# LightFlasher.net
KiCad netlist of a schematic drawn in EAGLE
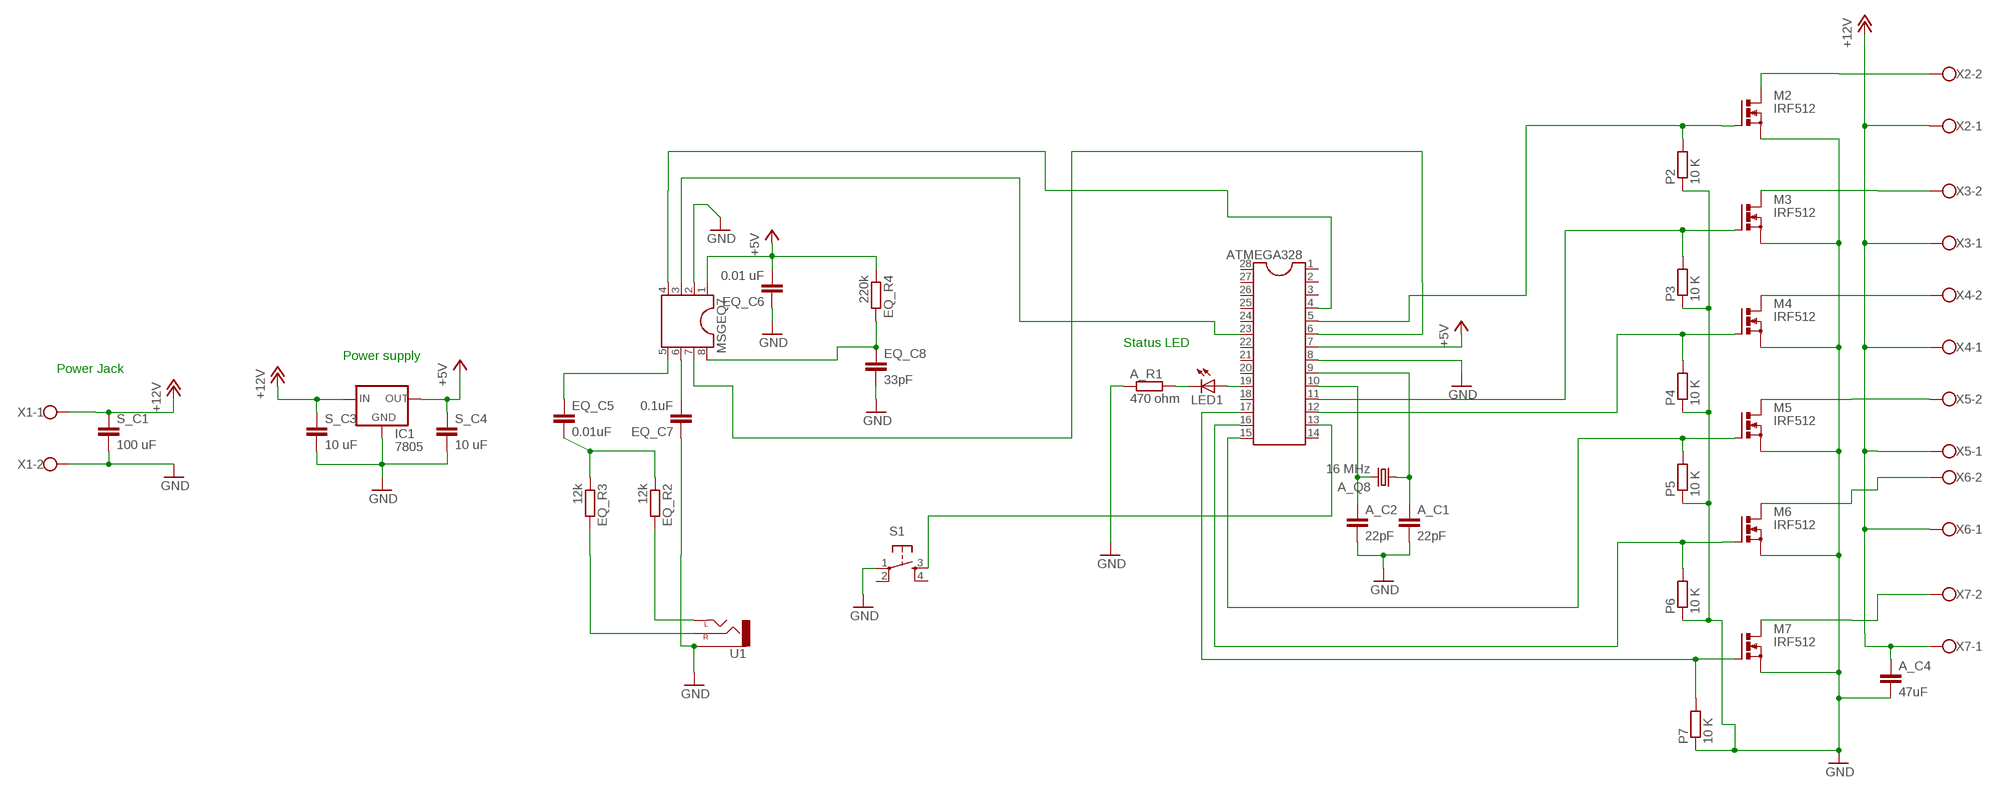
[diagram p0: schematic, sheet 1]

(export (version "E")
  (design (tool "Eeschema 10.0.6"))
  (components
    (comp (ref "ATMEGA328")
      (value "DIL28-3")
      (footprint "eagle-import:DIL28-3")
      (libsource (lib "eagle-import") (part "DIL28-3"))
    )
    (comp (ref "A_C1")
      (value "22pF")
      (footprint "eagle-import:C025-024X044")
      (libsource (lib "eagle-import") (part "C-EU025-024X044"))
    )
    (comp (ref "A_C2")
      (value "22pF")
      (footprint "eagle-import:C050-030X075")
      (libsource (lib "eagle-import") (part "C-EU050-030X075"))
    )
    (comp (ref "A_C4")
      (value "47uF")
      (footprint "eagle-import:C025-025X050")
      (libsource (lib "eagle-import") (part "C-EU025-025X050"))
    )
    (comp (ref "A_Q8")
      (value "16 MHz")
      (footprint "eagle-import:HC49_S")
      (libsource (lib "eagle-import") (part "CRYSTALHC49S"))
    )
    (comp (ref "A_R1")
      (value "470 ohm")
      (footprint "eagle-import:0204_5")
      (libsource (lib "eagle-import") (part "R-EU_0204/5"))
    )
    (comp (ref "EQ_C5")
      (value "0.01uF")
      (footprint "eagle-import:C025-024X044")
      (libsource (lib "eagle-import") (part "C-EU025-024X044"))
    )
    (comp (ref "EQ_C6")
      (value "0.01 uF")
      (footprint "eagle-import:C025-024X044")
      (libsource (lib "eagle-import") (part "C-EU025-024X044"))
    )
    (comp (ref "EQ_C7")
      (value "0.1uF")
      (footprint "eagle-import:C025-024X044")
      (libsource (lib "eagle-import") (part "C-EU025-024X044"))
    )
    (comp (ref "EQ_C8")
      (value "33pF")
      (footprint "eagle-import:C025-024X044")
      (libsource (lib "eagle-import") (part "C-EU025-024X044"))
    )
    (comp (ref "EQ_R2")
      (value "12k")
      (footprint "eagle-import:0204_5")
      (libsource (lib "eagle-import") (part "R-EU_0204/5"))
    )
    (comp (ref "EQ_R3")
      (value "12k")
      (footprint "eagle-import:0204_5")
      (libsource (lib "eagle-import") (part "R-EU_0204/5"))
    )
    (comp (ref "EQ_R4")
      (value "220k")
      (footprint "eagle-import:0204_5")
      (libsource (lib "eagle-import") (part "R-EU_0204/5"))
    )
    (comp (ref "IC1")
      (value "7805")
      (footprint "eagle-import:78XXS")
      (libsource (lib "eagle-import") (part "78XXS"))
    )
    (comp (ref "LED1")
      (value "LED3MM")
      (footprint "eagle-import:LED3MM")
      (libsource (lib "eagle-import") (part "LED3MM"))
    )
    (comp (ref "M2")
      (value "IRF512")
      (footprint "eagle-import:TO220BV")
      (libsource (lib "eagle-import") (part "IRF512"))
    )
    (comp (ref "M3")
      (value "IRF512")
      (footprint "eagle-import:TO220BV")
      (libsource (lib "eagle-import") (part "IRF512"))
    )
    (comp (ref "M4")
      (value "IRF512")
      (footprint "eagle-import:TO220BV")
      (libsource (lib "eagle-import") (part "IRF512"))
    )
    (comp (ref "M5")
      (value "IRF512")
      (footprint "eagle-import:TO220BV")
      (libsource (lib "eagle-import") (part "IRF512"))
    )
    (comp (ref "M6")
      (value "IRF512")
      (footprint "eagle-import:TO220BV")
      (libsource (lib "eagle-import") (part "IRF512"))
    )
    (comp (ref "M7")
      (value "IRF512")
      (footprint "eagle-import:TO220BV")
      (libsource (lib "eagle-import") (part "IRF512"))
    )
    (comp (ref "MSGEQ7")
      (value "DIL8S")
      (footprint "eagle-import:SOCKET-08")
      (libsource (lib "eagle-import") (part "DIL8S"))
    )
    (comp (ref "P2")
      (value "10 K")
      (footprint "eagle-import:0204_5")
      (libsource (lib "eagle-import") (part "R-EU_0204/5"))
    )
    (comp (ref "P3")
      (value "10 K")
      (footprint "eagle-import:0204_5")
      (libsource (lib "eagle-import") (part "R-EU_0204/5"))
    )
    (comp (ref "P4")
      (value "10 K")
      (footprint "eagle-import:0204_5")
      (libsource (lib "eagle-import") (part "R-EU_0204/5"))
    )
    (comp (ref "P5")
      (value "10 K")
      (footprint "eagle-import:0204_5")
      (libsource (lib "eagle-import") (part "R-EU_0204/5"))
    )
    (comp (ref "P6")
      (value "10 K")
      (footprint "eagle-import:0204_5")
      (libsource (lib "eagle-import") (part "R-EU_0204/5"))
    )
    (comp (ref "P7")
      (value "10 K")
      (footprint "eagle-import:0204_5")
      (libsource (lib "eagle-import") (part "R-EU_0204/5"))
    )
    (comp (ref "S1")
      (value "TAC_SWITCHPTH")
      (footprint "eagle-import:TACTILE-PTH")
      (libsource (lib "eagle-import") (part "TAC_SWITCHPTH"))
    )
    (comp (ref "S_C1")
      (value "100 uF")
      (footprint "eagle-import:C050-025X075")
      (libsource (lib "eagle-import") (part "C-EU050-025X075"))
    )
    (comp (ref "S_C3")
      (value "10 uF")
      (footprint "eagle-import:C025-024X044")
      (libsource (lib "eagle-import") (part "C-EU025-024X044"))
    )
    (comp (ref "S_C4")
      (value "10 uF")
      (footprint "eagle-import:C025-024X044")
      (libsource (lib "eagle-import") (part "C-EU025-024X044"))
    )
    (comp (ref "U1")
      (value "AUDIO-JACKPTH")
      (footprint "eagle-import:AUDIO-JACK")
      (libsource (lib "eagle-import") (part "AUDIO-JACKPTH"))
    )
    (comp (ref "X1")
      (value "W237-102")
      (footprint "eagle-import:W237-102")
      (fields (field (name "MPN") "237-102"))
      (libsource (lib "eagle-import") (part "W237-102"))
    )
    (comp (ref "X2")
      (value "W237-102")
      (footprint "eagle-import:W237-102")
      (fields (field (name "MPN") "237-102"))
      (libsource (lib "eagle-import") (part "W237-102"))
    )
    (comp (ref "X3")
      (value "W237-102")
      (footprint "eagle-import:W237-102")
      (fields (field (name "MPN") "237-102"))
      (libsource (lib "eagle-import") (part "W237-102"))
    )
    (comp (ref "X4")
      (value "W237-102")
      (footprint "eagle-import:W237-102")
      (fields (field (name "MPN") "237-102"))
      (libsource (lib "eagle-import") (part "W237-102"))
    )
    (comp (ref "X5")
      (value "W237-102")
      (footprint "eagle-import:W237-102")
      (fields (field (name "MPN") "237-102"))
      (libsource (lib "eagle-import") (part "W237-102"))
    )
    (comp (ref "X6")
      (value "W237-102")
      (footprint "eagle-import:W237-102")
      (fields (field (name "MPN") "237-102"))
      (libsource (lib "eagle-import") (part "W237-102"))
    )
    (comp (ref "X7")
      (value "W237-102")
      (footprint "eagle-import:W237-102")
      (fields (field (name "MPN") "237-102"))
      (libsource (lib "eagle-import") (part "W237-102"))
    )
  )
  (nets
    (net (code "1") (name "+5V") (class "Default")
      (node (ref "ATMEGA328") (pin "7") (pinfunction "7_7") (pintype "passive"))
      (node (ref "EQ_C6") (pin "2") (pinfunction "2_2") (pintype "passive"))
      (node (ref "EQ_R4") (pin "1") (pinfunction "1_1") (pintype "passive"))
      (node (ref "IC1") (pin "OUT") (pinfunction "OUT_OUT") (pintype "passive"))
      (node (ref "MSGEQ7") (pin "1") (pinfunction "1_1") (pintype "passive"))
      (node (ref "S_C4") (pin "1") (pinfunction "1_1") (pintype "passive"))
    )
    (net (code "2") (name "+12V") (class "Default")
      (node (ref "A_C4") (pin "1") (pinfunction "1_1") (pintype "passive"))
      (node (ref "IC1") (pin "IN") (pinfunction "IN_IN") (pintype "input"))
      (node (ref "S_C1") (pin "1") (pinfunction "1_1") (pintype "passive"))
      (node (ref "S_C3") (pin "1") (pinfunction "1_1") (pintype "passive"))
      (node (ref "X1") (pin "1") (pinfunction "KL_1") (pintype "passive"))
      (node (ref "X2") (pin "1") (pinfunction "KL_1") (pintype "passive"))
      (node (ref "X3") (pin "1") (pinfunction "KL_1") (pintype "passive"))
      (node (ref "X4") (pin "1") (pinfunction "KL_1") (pintype "passive"))
      (node (ref "X5") (pin "1") (pinfunction "KL_1") (pintype "passive"))
      (node (ref "X6") (pin "1") (pinfunction "KL_1") (pintype "passive"))
      (node (ref "X7") (pin "1") (pinfunction "KL_1") (pintype "passive"))
    )
    (net (code "3") (name "GND") (class "Default")
      (node (ref "ATMEGA328") (pin "8") (pinfunction "8_8") (pintype "passive"))
      (node (ref "A_C1") (pin "2") (pinfunction "2_2") (pintype "passive"))
      (node (ref "A_C2") (pin "2") (pinfunction "2_2") (pintype "passive"))
      (node (ref "A_C4") (pin "2") (pinfunction "2_2") (pintype "passive"))
      (node (ref "A_R1") (pin "1") (pinfunction "1_1") (pintype "passive"))
      (node (ref "EQ_C6") (pin "1") (pinfunction "1_1") (pintype "passive"))
      (node (ref "EQ_C7") (pin "1") (pinfunction "1_1") (pintype "passive"))
      (node (ref "EQ_C8") (pin "2") (pinfunction "2_2") (pintype "passive"))
      (node (ref "IC1") (pin "GND") (pinfunction "GND_GND") (pintype "input"))
      (node (ref "M2") (pin "S") (pinfunction "S_S") (pintype "passive"))
      (node (ref "M3") (pin "S") (pinfunction "S_S") (pintype "passive"))
      (node (ref "M4") (pin "S") (pinfunction "S_S") (pintype "passive"))
      (node (ref "M5") (pin "S") (pinfunction "S_S") (pintype "passive"))
      (node (ref "M6") (pin "S") (pinfunction "S_S") (pintype "passive"))
      (node (ref "M7") (pin "S") (pinfunction "S_S") (pintype "passive"))
      (node (ref "MSGEQ7") (pin "2") (pinfunction "2_2") (pintype "passive"))
      (node (ref "P2") (pin "1") (pinfunction "1_1") (pintype "passive"))
      (node (ref "P3") (pin "1") (pinfunction "1_1") (pintype "passive"))
      (node (ref "P4") (pin "1") (pinfunction "1_1") (pintype "passive"))
      (node (ref "P5") (pin "1") (pinfunction "1_1") (pintype "passive"))
      (node (ref "P6") (pin "1") (pinfunction "1_1") (pintype "passive"))
      (node (ref "P7") (pin "1") (pinfunction "1_1") (pintype "passive"))
      (node (ref "S1") (pin "1") (pinfunction "1_1") (pintype "passive"))
      (node (ref "S_C1") (pin "2") (pinfunction "2_2") (pintype "passive"))
      (node (ref "S_C3") (pin "2") (pinfunction "2_2") (pintype "passive"))
      (node (ref "S_C4") (pin "2") (pinfunction "2_2") (pintype "passive"))
      (node (ref "U1") (pin "SLEEVE") (pinfunction "SLEEVE_SLEEVE") (pintype "bidirectional"))
      (node (ref "X1") (pin "2") (pinfunction "KL_2") (pintype "passive"))
    )
    (net (code "4") (name "Net-(ATMEGA328-Pad4)") (class "Default")
      (node (ref "ATMEGA328") (pin "4") (pinfunction "4_4") (pintype "passive"))
      (node (ref "MSGEQ7") (pin "4") (pinfunction "4_4") (pintype "passive"))
    )
    (net (code "5") (name "Net-(ATMEGA328-Pad5)") (class "Default")
      (node (ref "ATMEGA328") (pin "5") (pinfunction "5_5") (pintype "passive"))
      (node (ref "M2") (pin "G") (pinfunction "G_G") (pintype "passive"))
      (node (ref "P2") (pin "2") (pinfunction "2_2") (pintype "passive"))
    )
    (net (code "6") (name "Net-(ATMEGA328-Pad6)") (class "Default")
      (node (ref "ATMEGA328") (pin "6") (pinfunction "6_6") (pintype "passive"))
      (node (ref "MSGEQ7") (pin "7") (pinfunction "7_7") (pintype "passive"))
    )
    (net (code "7") (name "Net-(ATMEGA328-Pad9)") (class "Default")
      (node (ref "ATMEGA328") (pin "9") (pinfunction "9_9") (pintype "passive"))
      (node (ref "A_C1") (pin "1") (pinfunction "1_1") (pintype "passive"))
      (node (ref "A_Q8") (pin "1") (pinfunction "1_1") (pintype "passive"))
    )
    (net (code "8") (name "Net-(ATMEGA328-Pad10)") (class "Default")
      (node (ref "ATMEGA328") (pin "10") (pinfunction "10_10") (pintype "passive"))
      (node (ref "A_C2") (pin "1") (pinfunction "1_1") (pintype "passive"))
      (node (ref "A_Q8") (pin "2") (pinfunction "2_2") (pintype "passive"))
    )
    (net (code "9") (name "Net-(ATMEGA328-Pad11)") (class "Default")
      (node (ref "ATMEGA328") (pin "11") (pinfunction "11_11") (pintype "passive"))
      (node (ref "M3") (pin "G") (pinfunction "G_G") (pintype "passive"))
      (node (ref "P3") (pin "2") (pinfunction "2_2") (pintype "passive"))
    )
    (net (code "10") (name "Net-(ATMEGA328-Pad12)") (class "Default")
      (node (ref "ATMEGA328") (pin "12") (pinfunction "12_12") (pintype "passive"))
      (node (ref "M4") (pin "G") (pinfunction "G_G") (pintype "passive"))
      (node (ref "P4") (pin "2") (pinfunction "2_2") (pintype "passive"))
    )
    (net (code "11") (name "Net-(ATMEGA328-Pad13)") (class "Default")
      (node (ref "ATMEGA328") (pin "13") (pinfunction "13_13") (pintype "passive"))
      (node (ref "S1") (pin "3") (pinfunction "3_3") (pintype "passive"))
    )
    (net (code "12") (name "Net-(ATMEGA328-Pad15)") (class "Default")
      (node (ref "ATMEGA328") (pin "15") (pinfunction "15_15") (pintype "passive"))
      (node (ref "M5") (pin "G") (pinfunction "G_G") (pintype "passive"))
      (node (ref "P5") (pin "2") (pinfunction "2_2") (pintype "passive"))
    )
    (net (code "13") (name "Net-(ATMEGA328-Pad16)") (class "Default")
      (node (ref "ATMEGA328") (pin "16") (pinfunction "16_16") (pintype "passive"))
      (node (ref "M6") (pin "G") (pinfunction "G_G") (pintype "passive"))
      (node (ref "P6") (pin "2") (pinfunction "2_2") (pintype "passive"))
    )
    (net (code "14") (name "Net-(ATMEGA328-Pad17)") (class "Default")
      (node (ref "ATMEGA328") (pin "17") (pinfunction "17_17") (pintype "passive"))
      (node (ref "M7") (pin "G") (pinfunction "G_G") (pintype "passive"))
      (node (ref "P7") (pin "2") (pinfunction "2_2") (pintype "passive"))
    )
    (net (code "15") (name "Net-(ATMEGA328-Pad19)") (class "Default")
      (node (ref "ATMEGA328") (pin "19") (pinfunction "19_19") (pintype "passive"))
      (node (ref "LED1") (pin "A") (pinfunction "A_A") (pintype "passive"))
    )
    (net (code "16") (name "Net-(ATMEGA328-Pad23)") (class "Default")
      (node (ref "ATMEGA328") (pin "23") (pinfunction "23_23") (pintype "passive"))
      (node (ref "MSGEQ7") (pin "3") (pinfunction "3_3") (pintype "passive"))
    )
    (net (code "17") (name "Net-(EQ_C5-Pad1)") (class "Default")
      (node (ref "EQ_C5") (pin "1") (pinfunction "1_1") (pintype "passive"))
      (node (ref "MSGEQ7") (pin "5") (pinfunction "5_5") (pintype "passive"))
    )
    (net (code "18") (name "Net-(EQ_C5-Pad2)") (class "Default")
      (node (ref "EQ_C5") (pin "2") (pinfunction "2_2") (pintype "passive"))
      (node (ref "EQ_R2") (pin "1") (pinfunction "1_1") (pintype "passive"))
      (node (ref "EQ_R3") (pin "1") (pinfunction "1_1") (pintype "passive"))
    )
    (net (code "19") (name "Net-(EQ_C7-Pad2)") (class "Default")
      (node (ref "EQ_C7") (pin "2") (pinfunction "2_2") (pintype "passive"))
      (node (ref "MSGEQ7") (pin "6") (pinfunction "6_6") (pintype "passive"))
    )
    (net (code "20") (name "Net-(EQ_C8-Pad1)") (class "Default")
      (node (ref "EQ_C8") (pin "1") (pinfunction "1_1") (pintype "passive"))
      (node (ref "EQ_R4") (pin "2") (pinfunction "2_2") (pintype "passive"))
      (node (ref "MSGEQ7") (pin "8") (pinfunction "8_8") (pintype "passive"))
    )
    (net (code "21") (name "Net-(LED1-C)") (class "Default")
      (node (ref "A_R1") (pin "2") (pinfunction "2_2") (pintype "passive"))
      (node (ref "LED1") (pin "K") (pinfunction "C_K") (pintype "passive"))
    )
    (net (code "22") (name "Net-(U1-LEFT)") (class "Default")
      (node (ref "EQ_R2") (pin "2") (pinfunction "2_2") (pintype "passive"))
      (node (ref "U1") (pin "TIP") (pinfunction "LEFT_TIP") (pintype "bidirectional"))
    )
    (net (code "23") (name "Net-(U1-RIGHT)") (class "Default")
      (node (ref "EQ_R3") (pin "2") (pinfunction "2_2") (pintype "passive"))
      (node (ref "U1") (pin "RING") (pinfunction "RIGHT_RING") (pintype "bidirectional"))
    )
    (net (code "24") (name "Net-(X2B-KL)") (class "Default")
      (node (ref "M2") (pin "D") (pinfunction "D_D") (pintype "passive"))
      (node (ref "X2") (pin "2") (pinfunction "KL_2") (pintype "passive"))
    )
    (net (code "25") (name "Net-(X3B-KL)") (class "Default")
      (node (ref "M3") (pin "D") (pinfunction "D_D") (pintype "passive"))
      (node (ref "X3") (pin "2") (pinfunction "KL_2") (pintype "passive"))
    )
    (net (code "26") (name "Net-(X4B-KL)") (class "Default")
      (node (ref "M4") (pin "D") (pinfunction "D_D") (pintype "passive"))
      (node (ref "X4") (pin "2") (pinfunction "KL_2") (pintype "passive"))
    )
    (net (code "27") (name "Net-(X5B-KL)") (class "Default")
      (node (ref "M5") (pin "D") (pinfunction "D_D") (pintype "passive"))
      (node (ref "X5") (pin "2") (pinfunction "KL_2") (pintype "passive"))
    )
    (net (code "28") (name "Net-(X6B-KL)") (class "Default")
      (node (ref "M6") (pin "D") (pinfunction "D_D") (pintype "passive"))
      (node (ref "X6") (pin "2") (pinfunction "KL_2") (pintype "passive"))
    )
    (net (code "29") (name "Net-(X7B-KL)") (class "Default")
      (node (ref "M7") (pin "D") (pinfunction "D_D") (pintype "passive"))
      (node (ref "X7") (pin "2") (pinfunction "KL_2") (pintype "passive"))
    )
    (net (code "30") (name "unconnected-(ATMEGA328-Pad1)") (class "Default")
      (node (ref "ATMEGA328") (pin "1") (pinfunction "1_1") (pintype "passive"))
    )
    (net (code "31") (name "unconnected-(ATMEGA328-Pad2)") (class "Default")
      (node (ref "ATMEGA328") (pin "2") (pinfunction "2_2") (pintype "passive"))
    )
    (net (code "32") (name "unconnected-(ATMEGA328-Pad3)") (class "Default")
      (node (ref "ATMEGA328") (pin "3") (pinfunction "3_3") (pintype "passive"))
    )
    (net (code "33") (name "unconnected-(ATMEGA328-Pad14)") (class "Default")
      (node (ref "ATMEGA328") (pin "14") (pinfunction "14_14") (pintype "passive"))
    )
    (net (code "34") (name "unconnected-(ATMEGA328-Pad18)") (class "Default")
      (node (ref "ATMEGA328") (pin "18") (pinfunction "18_18") (pintype "passive"))
    )
    (net (code "35") (name "unconnected-(ATMEGA328-Pad20)") (class "Default")
      (node (ref "ATMEGA328") (pin "20") (pinfunction "20_20") (pintype "passive"))
    )
    (net (code "36") (name "unconnected-(ATMEGA328-Pad21)") (class "Default")
      (node (ref "ATMEGA328") (pin "21") (pinfunction "21_21") (pintype "passive"))
    )
    (net (code "37") (name "unconnected-(ATMEGA328-Pad22)") (class "Default")
      (node (ref "ATMEGA328") (pin "22") (pinfunction "22_22") (pintype "passive"))
    )
    (net (code "38") (name "unconnected-(ATMEGA328-Pad24)") (class "Default")
      (node (ref "ATMEGA328") (pin "24") (pinfunction "24_24") (pintype "passive"))
    )
    (net (code "39") (name "unconnected-(ATMEGA328-Pad25)") (class "Default")
      (node (ref "ATMEGA328") (pin "25") (pinfunction "25_25") (pintype "passive"))
    )
    (net (code "40") (name "unconnected-(ATMEGA328-Pad26)") (class "Default")
      (node (ref "ATMEGA328") (pin "26") (pinfunction "26_26") (pintype "passive"))
    )
    (net (code "41") (name "unconnected-(ATMEGA328-Pad27)") (class "Default")
      (node (ref "ATMEGA328") (pin "27") (pinfunction "27_27") (pintype "passive"))
    )
    (net (code "42") (name "unconnected-(ATMEGA328-Pad28)") (class "Default")
      (node (ref "ATMEGA328") (pin "28") (pinfunction "28_28") (pintype "passive"))
    )
    (net (code "43") (name "unconnected-(S1-Pad2)") (class "Default")
      (node (ref "S1") (pin "2") (pinfunction "2_2") (pintype "passive"))
    )
    (net (code "44") (name "unconnected-(S1-Pad4)") (class "Default")
      (node (ref "S1") (pin "4") (pinfunction "4_4") (pintype "passive"))
    )
  )
)
